# MCB-NINA-B1-v2_0_0.net
KiCad netlist of a schematic drawn in EAGLE
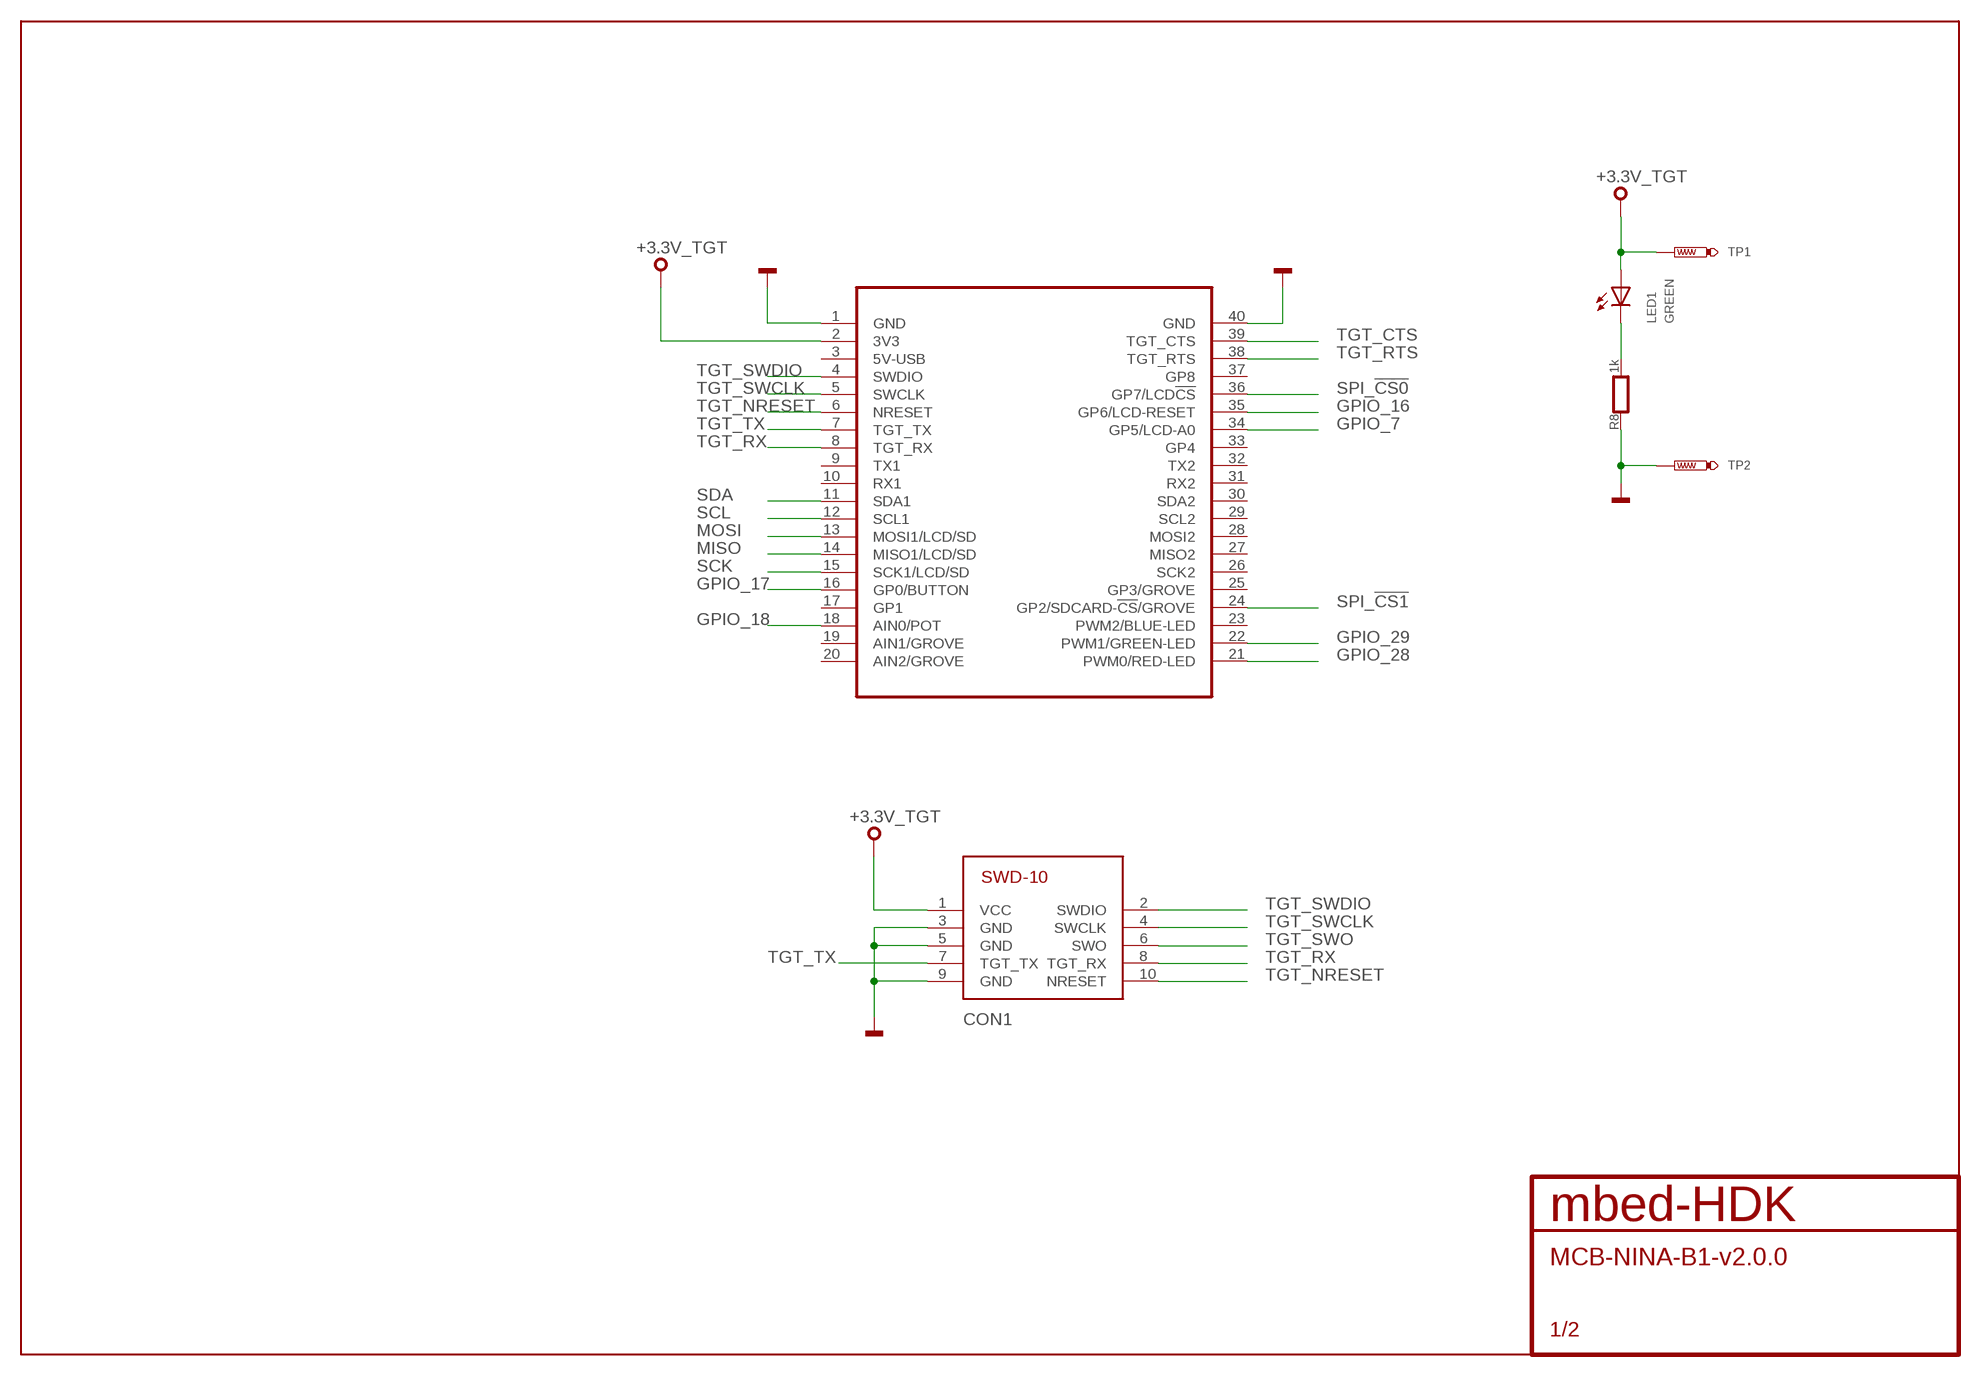
[diagram p0: schematic, sheet 1]
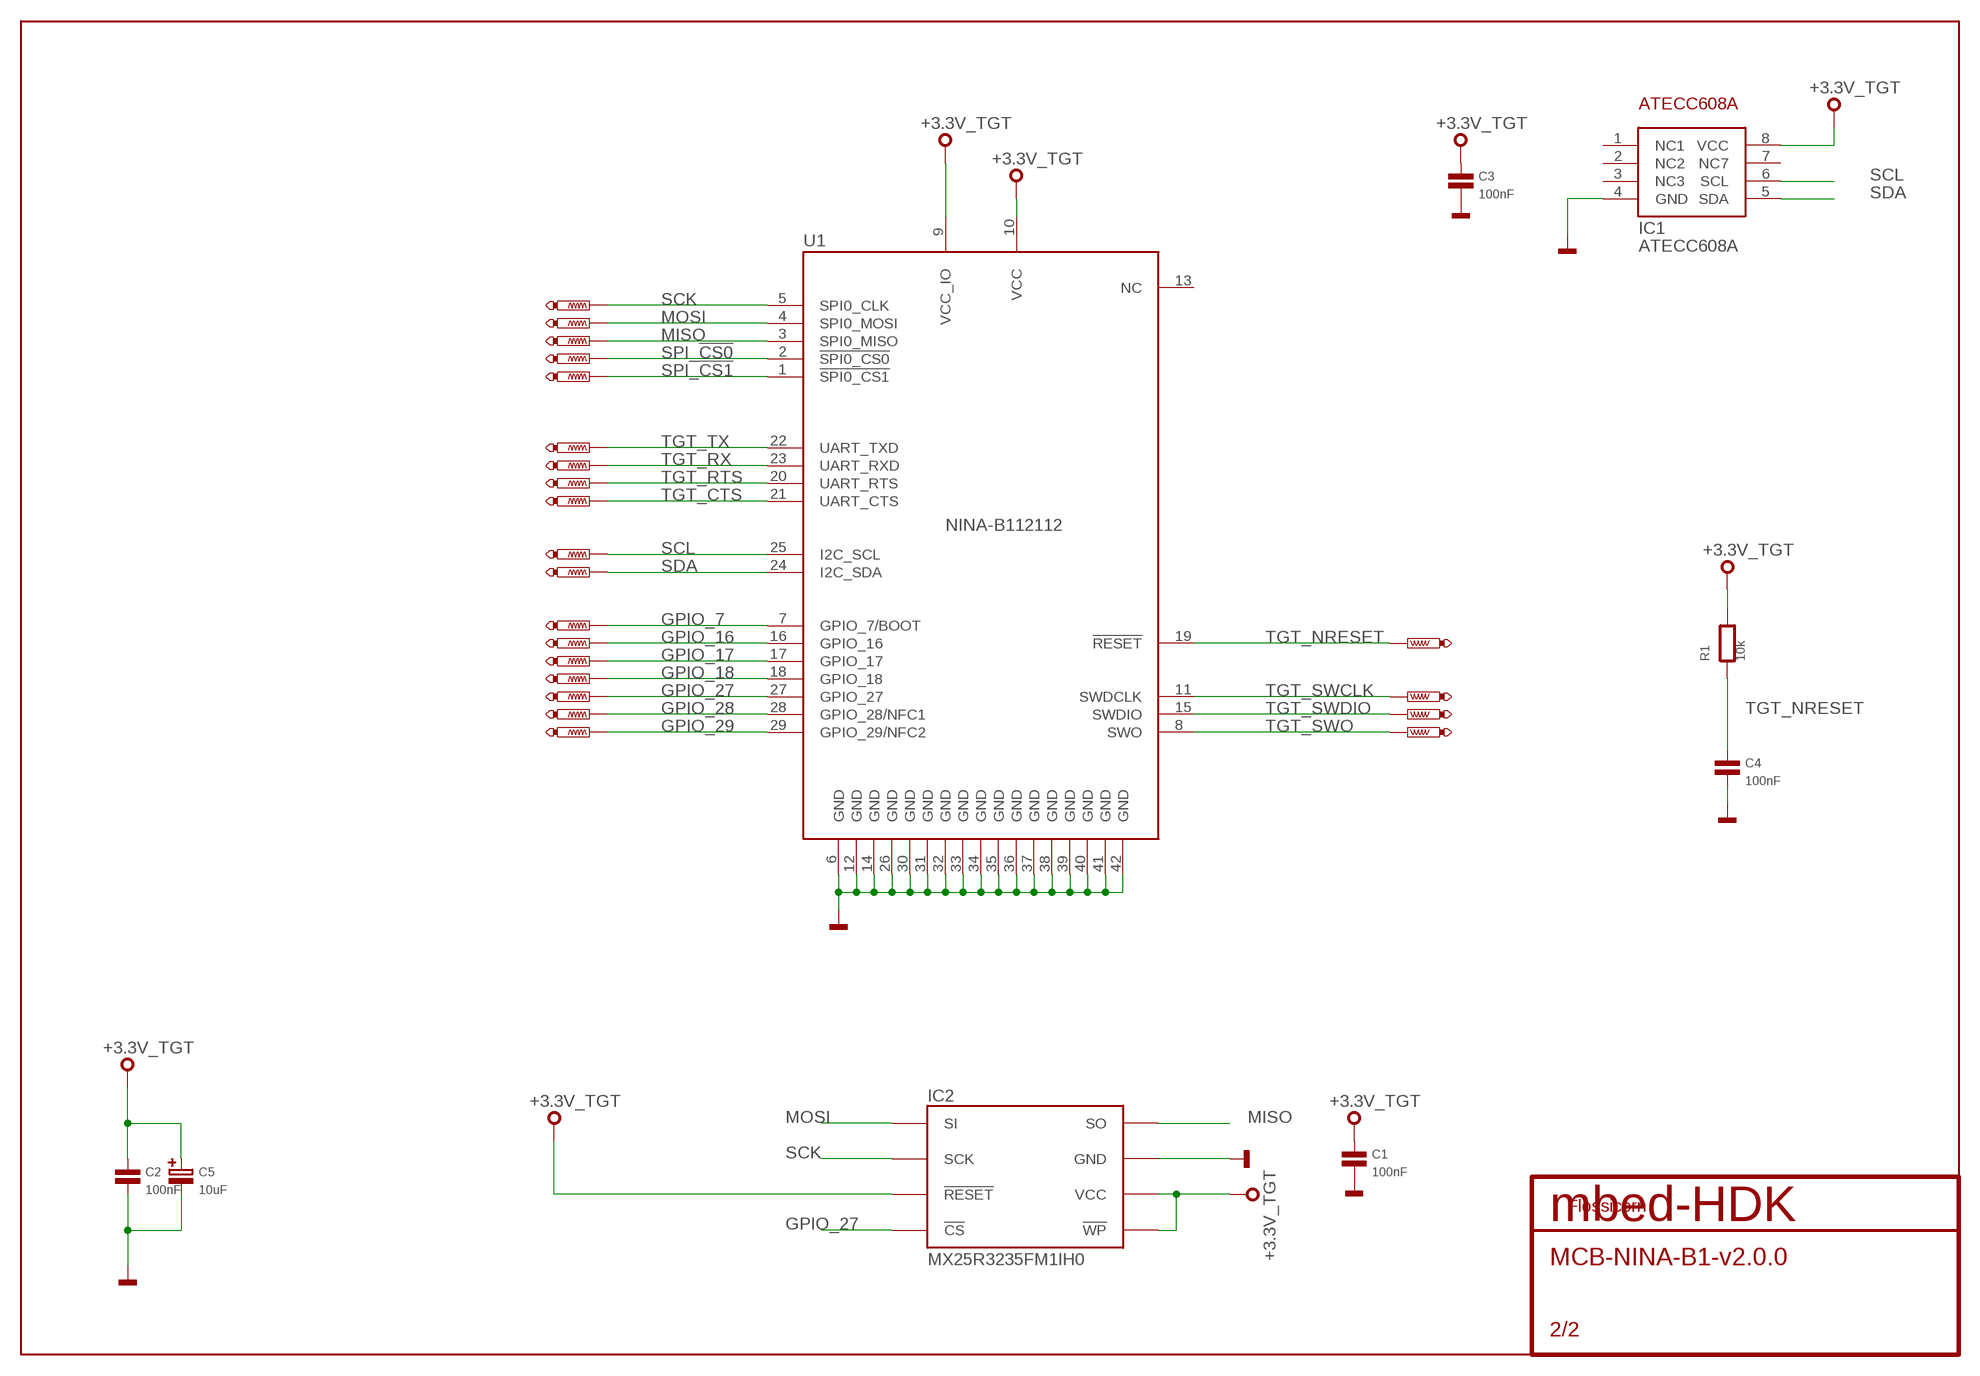
[diagram p1: schematic, sheet 2]

(export (version "E")
  (design (tool "Eeschema 10.0.6"))
  (components
    (comp (ref "C1")
      (value "100nF")
      (footprint "eagle-import:0603")
      (libsource (lib "eagle-import") (part "CAPACITOR0603"))
    )
    (comp (ref "C2")
      (value "100nF")
      (footprint "eagle-import:0603")
      (libsource (lib "eagle-import") (part "CAPACITOR0603"))
    )
    (comp (ref "C3")
      (value "100nF")
      (footprint "eagle-import:0603")
      (libsource (lib "eagle-import") (part "CAPACITOR0603"))
    )
    (comp (ref "C4")
      (value "100nF")
      (footprint "eagle-import:0603")
      (libsource (lib "eagle-import") (part "CAPACITOR0603"))
    )
    (comp (ref "C5")
      (value "10uF")
      (footprint "eagle-import:SMC_B")
      (fields (field (name "MF") "Kemet"))
      (libsource (lib "eagle-import") (part "CAPACITOR-POLARISEDB"))
    )
    (comp (ref "IC1")
      (value "ATECC608A")
      (footprint "eagle-import:SO8")
      (libsource (lib "eagle-import") (part "ATECC608A"))
    )
    (comp (ref "IC2")
      (value "MX25R3235FM1IH0")
      (footprint "eagle-import:SO8")
      (fields (field (name "MF") "Macronix"))
      (libsource (lib "eagle-import") (part "MX25R3235FM1IH0"))
    )
    (comp (ref "R1")
      (value "10k")
      (footprint "eagle-import:0603")
      (libsource (lib "eagle-import") (part "RESISTOR0603"))
    )
    (comp (ref "SS1")
      (value "FLOSSICORN0.5")
      (footprint "eagle-import:FLOSSICORN-0.5")
      (libsource (lib "eagle-import") (part "FLOSSICORN0.5"))
    )
    (comp (ref "TP3")
      (value "PTR1B1,27")
      (footprint "eagle-import:B1,27")
      (libsource (lib "eagle-import") (part "PTR1B1,27"))
    )
    (comp (ref "TP4")
      (value "PTR1B1,27")
      (footprint "eagle-import:B1,27")
      (libsource (lib "eagle-import") (part "PTR1B1,27"))
    )
    (comp (ref "TP5")
      (value "PTR1B1,27")
      (footprint "eagle-import:B1,27")
      (libsource (lib "eagle-import") (part "PTR1B1,27"))
    )
    (comp (ref "TP6")
      (value "PTR1B1,27")
      (footprint "eagle-import:B1,27")
      (libsource (lib "eagle-import") (part "PTR1B1,27"))
    )
    (comp (ref "TP7")
      (value "PTR1B1,27")
      (footprint "eagle-import:B1,27")
      (libsource (lib "eagle-import") (part "PTR1B1,27"))
    )
    (comp (ref "TP8")
      (value "PTR1B1,27")
      (footprint "eagle-import:B1,27")
      (libsource (lib "eagle-import") (part "PTR1B1,27"))
    )
    (comp (ref "TP9")
      (value "PTR1B1,27")
      (footprint "eagle-import:B1,27")
      (libsource (lib "eagle-import") (part "PTR1B1,27"))
    )
    (comp (ref "TP10")
      (value "PTR1B1,27")
      (footprint "eagle-import:B1,27")
      (libsource (lib "eagle-import") (part "PTR1B1,27"))
    )
    (comp (ref "TP11")
      (value "PTR1B1,27")
      (footprint "eagle-import:B1,27")
      (libsource (lib "eagle-import") (part "PTR1B1,27"))
    )
    (comp (ref "TP12")
      (value "PTR1B1,27")
      (footprint "eagle-import:B1,27")
      (libsource (lib "eagle-import") (part "PTR1B1,27"))
    )
    (comp (ref "TP13")
      (value "PTR1B1,27")
      (footprint "eagle-import:B1,27")
      (libsource (lib "eagle-import") (part "PTR1B1,27"))
    )
    (comp (ref "TP14")
      (value "PTR1B1,27")
      (footprint "eagle-import:B1,27")
      (libsource (lib "eagle-import") (part "PTR1B1,27"))
    )
    (comp (ref "TP15")
      (value "PTR1B1,27")
      (footprint "eagle-import:B1,27")
      (libsource (lib "eagle-import") (part "PTR1B1,27"))
    )
    (comp (ref "TP16")
      (value "PTR1B1,27")
      (footprint "eagle-import:B1,27")
      (libsource (lib "eagle-import") (part "PTR1B1,27"))
    )
    (comp (ref "TP17")
      (value "PTR1B1,27")
      (footprint "eagle-import:B1,27")
      (libsource (lib "eagle-import") (part "PTR1B1,27"))
    )
    (comp (ref "TP18")
      (value "PTR1B1,27")
      (footprint "eagle-import:B1,27")
      (libsource (lib "eagle-import") (part "PTR1B1,27"))
    )
    (comp (ref "TP19")
      (value "PTR1B1,27")
      (footprint "eagle-import:B1,27")
      (libsource (lib "eagle-import") (part "PTR1B1,27"))
    )
    (comp (ref "TP20")
      (value "PTR1B1,27")
      (footprint "eagle-import:B1,27")
      (libsource (lib "eagle-import") (part "PTR1B1,27"))
    )
    (comp (ref "TP21")
      (value "PTR1B1,27")
      (footprint "eagle-import:B1,27")
      (libsource (lib "eagle-import") (part "PTR1B1,27"))
    )
    (comp (ref "TP22")
      (value "PTR1B1,27")
      (footprint "eagle-import:B1,27")
      (libsource (lib "eagle-import") (part "PTR1B1,27"))
    )
    (comp (ref "TP23")
      (value "PTR1B1,27")
      (footprint "eagle-import:B1,27")
      (libsource (lib "eagle-import") (part "PTR1B1,27"))
    )
    (comp (ref "TP24")
      (value "PTR1B1,27")
      (footprint "eagle-import:B1,27")
      (libsource (lib "eagle-import") (part "PTR1B1,27"))
    )
    (comp (ref "U1")
      (value "NINA-B112112")
      (footprint "eagle-import:NINA112-42")
      (libsource (lib "eagle-import") (part "NINA-B112112"))
    )
    (comp (ref "CON1")
      (value "SWD-10/TC2050_SMD")
      (footprint "eagle-import:FTSH-105-02")
      (libsource (lib "eagle-import") (part "SWD-10/TC2050_SMD"))
    )
    (comp (ref "LED1")
      (value "GREEN")
      (footprint "eagle-import:CHIPLED_0603")
      (fields (field (name "MF") "Wurth Electronics Inc"))
      (libsource (lib "eagle-import") (part "SMD_LED0603"))
    )
    (comp (ref "MOD1")
      (value "MODULE_DAUGHTER")
      (footprint "eagle-import:MODULE_DAUGHTER")
      (libsource (lib "eagle-import") (part "MODULE_DAUGHTER"))
    )
    (comp (ref "R8")
      (value "1k")
      (footprint "eagle-import:0603")
      (libsource (lib "eagle-import") (part "RESISTOR0603"))
    )
    (comp (ref "TP1")
      (value "TEST-POINT-50R-PTH")
      (footprint "eagle-import:TP50-PTH")
      (libsource (lib "eagle-import") (part "TEST-POINT-50R-PTH"))
    )
    (comp (ref "TP2")
      (value "TEST-POINT-50R-PTH")
      (footprint "eagle-import:TP50-PTH")
      (libsource (lib "eagle-import") (part "TEST-POINT-50R-PTH"))
    )
  )
  (nets
    (net (code "1") (name "+3.3V_TGT") (class "Default")
      (node (ref "C1") (pin "1") (pinfunction "P$1_1") (pintype "passive"))
      (node (ref "C2") (pin "1") (pinfunction "P$1_1") (pintype "passive"))
      (node (ref "C3") (pin "1") (pinfunction "P$1_1") (pintype "passive"))
      (node (ref "C5") (pin "+") (pinfunction "+_+") (pintype "passive"))
      (node (ref "CON1") (pin "1") (pinfunction "VCC_1") (pintype "bidirectional"))
      (node (ref "IC1") (pin "8") (pinfunction "VCC_8") (pintype "bidirectional"))
      (node (ref "IC2") (pin "3") (pinfunction "~{WP}_3") (pintype "bidirectional"))
      (node (ref "IC2") (pin "7") (pinfunction "~{RESET}_7") (pintype "bidirectional"))
      (node (ref "IC2") (pin "8") (pinfunction "VCC_8") (pintype "bidirectional"))
      (node (ref "LED1") (pin "A") (pinfunction "A_A") (pintype "passive"))
      (node (ref "MOD1") (pin "2") (pinfunction "3V3_2") (pintype "bidirectional"))
      (node (ref "R1") (pin "2") (pinfunction "P$2_2") (pintype "passive"))
      (node (ref "TP1") (pin "TP") (pinfunction "TP_TP") (pintype "input"))
      (node (ref "U1") (pin "10") (pinfunction "VCC_10") (pintype "power_in"))
      (node (ref "U1") (pin "9") (pinfunction "VCC_IO_9") (pintype "power_in"))
    )
    (net (code "2") (name "GND") (class "Default")
      (node (ref "C1") (pin "2") (pinfunction "P$2_2") (pintype "passive"))
      (node (ref "C2") (pin "2") (pinfunction "P$2_2") (pintype "passive"))
      (node (ref "C3") (pin "2") (pinfunction "P$2_2") (pintype "passive"))
      (node (ref "C4") (pin "2") (pinfunction "P$2_2") (pintype "passive"))
      (node (ref "C5") (pin "-") (pinfunction "-_-") (pintype "passive"))
      (node (ref "CON1") (pin "3") (pinfunction "GND_3") (pintype "bidirectional"))
      (node (ref "CON1") (pin "5") (pinfunction "GND_5") (pintype "bidirectional"))
      (node (ref "CON1") (pin "9") (pinfunction "GND_9") (pintype "bidirectional"))
      (node (ref "IC1") (pin "4") (pinfunction "GND_4") (pintype "bidirectional"))
      (node (ref "IC2") (pin "4") (pinfunction "GND_4") (pintype "bidirectional"))
      (node (ref "MOD1") (pin "1") (pinfunction "GND_1") (pintype "bidirectional"))
      (node (ref "MOD1") (pin "40") (pinfunction "GND_40") (pintype "bidirectional"))
      (node (ref "R8") (pin "1") (pinfunction "P$1_1") (pintype "passive"))
      (node (ref "TP2") (pin "TP") (pinfunction "TP_TP") (pintype "input"))
      (node (ref "U1") (pin "12") (pinfunction "GND_12") (pintype "power_in"))
      (node (ref "U1") (pin "14") (pinfunction "GND_14") (pintype "power_in"))
      (node (ref "U1") (pin "26") (pinfunction "GND_26") (pintype "power_in"))
      (node (ref "U1") (pin "30") (pinfunction "GND_30") (pintype "power_in"))
      (node (ref "U1") (pin "31") (pinfunction "GND_31") (pintype "power_in"))
      (node (ref "U1") (pin "32") (pinfunction "GND_32") (pintype "power_in"))
      (node (ref "U1") (pin "33") (pinfunction "GND_33") (pintype "power_in"))
      (node (ref "U1") (pin "34") (pinfunction "GND_34") (pintype "power_in"))
      (node (ref "U1") (pin "35") (pinfunction "GND_35") (pintype "power_in"))
      (node (ref "U1") (pin "36") (pinfunction "GND_36") (pintype "power_in"))
      (node (ref "U1") (pin "37") (pinfunction "GND_37") (pintype "power_in"))
      (node (ref "U1") (pin "38") (pinfunction "GND_38") (pintype "power_in"))
      (node (ref "U1") (pin "39") (pinfunction "GND_39") (pintype "power_in"))
      (node (ref "U1") (pin "40") (pinfunction "GND_40") (pintype "power_in"))
      (node (ref "U1") (pin "41") (pinfunction "GND_41") (pintype "power_in"))
      (node (ref "U1") (pin "42") (pinfunction "GND_42") (pintype "power_in"))
      (node (ref "U1") (pin "6") (pinfunction "GND_6") (pintype "power_in"))
    )
    (net (code "3") (name "GPIO_7") (class "Default")
      (node (ref "MOD1") (pin "34") (pinfunction "GP5/LCD-A0_34") (pintype "bidirectional"))
      (node (ref "TP14") (pin "TP") (pinfunction "TP_TP") (pintype "input"))
      (node (ref "U1") (pin "7") (pinfunction "GPIO_7/BOOT_7") (pintype "bidirectional"))
    )
    (net (code "4") (name "GPIO_16") (class "Default")
      (node (ref "MOD1") (pin "35") (pinfunction "GP6/LCD-RESET_35") (pintype "bidirectional"))
      (node (ref "TP15") (pin "TP") (pinfunction "TP_TP") (pintype "input"))
      (node (ref "U1") (pin "16") (pinfunction "GPIO_16_16") (pintype "bidirectional"))
    )
    (net (code "5") (name "GPIO_17") (class "Default")
      (node (ref "MOD1") (pin "16") (pinfunction "GP0/BUTTON_16") (pintype "bidirectional"))
      (node (ref "TP16") (pin "TP") (pinfunction "TP_TP") (pintype "input"))
      (node (ref "U1") (pin "17") (pinfunction "GPIO_17_17") (pintype "bidirectional"))
    )
    (net (code "6") (name "GPIO_18") (class "Default")
      (node (ref "MOD1") (pin "18") (pinfunction "AIN0/POT_18") (pintype "bidirectional"))
      (node (ref "TP17") (pin "TP") (pinfunction "TP_TP") (pintype "input"))
      (node (ref "U1") (pin "18") (pinfunction "GPIO_18_18") (pintype "bidirectional"))
    )
    (net (code "7") (name "GPIO_27") (class "Default")
      (node (ref "IC2") (pin "1") (pinfunction "~{CS}_1") (pintype "bidirectional"))
      (node (ref "TP18") (pin "TP") (pinfunction "TP_TP") (pintype "input"))
      (node (ref "U1") (pin "27") (pinfunction "GPIO_27_27") (pintype "bidirectional"))
    )
    (net (code "8") (name "GPIO_28") (class "Default")
      (node (ref "MOD1") (pin "21") (pinfunction "PWM0/RED-LED_21") (pintype "bidirectional"))
      (node (ref "TP19") (pin "TP") (pinfunction "TP_TP") (pintype "input"))
      (node (ref "U1") (pin "28") (pinfunction "GPIO_28/NFC1_28") (pintype "bidirectional"))
    )
    (net (code "9") (name "GPIO_29") (class "Default")
      (node (ref "MOD1") (pin "22") (pinfunction "PWM1/GREEN-LED_22") (pintype "bidirectional"))
      (node (ref "TP20") (pin "TP") (pinfunction "TP_TP") (pintype "input"))
      (node (ref "U1") (pin "29") (pinfunction "GPIO_29/NFC2_29") (pintype "bidirectional"))
    )
    (net (code "10") (name "MISO") (class "Default")
      (node (ref "IC2") (pin "2") (pinfunction "SO_2") (pintype "bidirectional"))
      (node (ref "MOD1") (pin "14") (pinfunction "MISO1/LCD/SD_14") (pintype "bidirectional"))
      (node (ref "TP5") (pin "TP") (pinfunction "TP_TP") (pintype "input"))
      (node (ref "U1") (pin "3") (pinfunction "SPI0_MISO_3") (pintype "bidirectional"))
    )
    (net (code "11") (name "MOSI") (class "Default")
      (node (ref "IC2") (pin "5") (pinfunction "SI_5") (pintype "bidirectional"))
      (node (ref "MOD1") (pin "13") (pinfunction "MOSI1/LCD/SD_13") (pintype "bidirectional"))
      (node (ref "TP4") (pin "TP") (pinfunction "TP_TP") (pintype "input"))
      (node (ref "U1") (pin "4") (pinfunction "SPI0_MOSI_4") (pintype "bidirectional"))
    )
    (net (code "12") (name "Net-(R8-P$2)") (class "Default")
      (node (ref "LED1") (pin "C") (pinfunction "C_C") (pintype "passive"))
      (node (ref "R8") (pin "2") (pinfunction "P$2_2") (pintype "passive"))
    )
    (net (code "13") (name "SCK") (class "Default")
      (node (ref "IC2") (pin "6") (pinfunction "SCK_6") (pintype "bidirectional"))
      (node (ref "MOD1") (pin "15") (pinfunction "SCK1/LCD/SD_15") (pintype "bidirectional"))
      (node (ref "TP3") (pin "TP") (pinfunction "TP_TP") (pintype "input"))
      (node (ref "U1") (pin "5") (pinfunction "SPI0_CLK_5") (pintype "bidirectional"))
    )
    (net (code "14") (name "SCL") (class "Default")
      (node (ref "IC1") (pin "6") (pinfunction "SCL_6") (pintype "bidirectional"))
      (node (ref "MOD1") (pin "12") (pinfunction "SCL1_12") (pintype "bidirectional"))
      (node (ref "TP12") (pin "TP") (pinfunction "TP_TP") (pintype "input"))
      (node (ref "U1") (pin "25") (pinfunction "I2C_SCL_25") (pintype "bidirectional"))
    )
    (net (code "15") (name "SDA") (class "Default")
      (node (ref "IC1") (pin "5") (pinfunction "SDA_5") (pintype "bidirectional"))
      (node (ref "MOD1") (pin "11") (pinfunction "SDA1_11") (pintype "bidirectional"))
      (node (ref "TP13") (pin "TP") (pinfunction "TP_TP") (pintype "input"))
      (node (ref "U1") (pin "24") (pinfunction "I2C_SDA_24") (pintype "bidirectional"))
    )
    (net (code "16") (name "SPI_~{CS0}") (class "Default")
      (node (ref "MOD1") (pin "36") (pinfunction "GP7/LCD~{CS}_36") (pintype "bidirectional"))
      (node (ref "TP6") (pin "TP") (pinfunction "TP_TP") (pintype "input"))
      (node (ref "U1") (pin "2") (pinfunction "~{SPI0_CS0}_2") (pintype "bidirectional"))
    )
    (net (code "17") (name "SPI_~{CS1}") (class "Default")
      (node (ref "MOD1") (pin "24") (pinfunction "GP2/SDCARD-~{CS}/GROVE_24") (pintype "bidirectional"))
      (node (ref "TP7") (pin "TP") (pinfunction "TP_TP") (pintype "input"))
      (node (ref "U1") (pin "1") (pinfunction "~{SPI0_CS1}_1") (pintype "output"))
    )
    (net (code "18") (name "TGT_CTS") (class "Default")
      (node (ref "MOD1") (pin "39") (pinfunction "TGT_CTS_39") (pintype "bidirectional"))
      (node (ref "TP11") (pin "TP") (pinfunction "TP_TP") (pintype "input"))
      (node (ref "U1") (pin "21") (pinfunction "UART_CTS_21") (pintype "bidirectional"))
    )
    (net (code "19") (name "TGT_NRESET") (class "Default")
      (node (ref "C4") (pin "1") (pinfunction "P$1_1") (pintype "passive"))
      (node (ref "CON1") (pin "10") (pinfunction "NRESET_10") (pintype "bidirectional"))
      (node (ref "MOD1") (pin "6") (pinfunction "NRESET_6") (pintype "bidirectional"))
      (node (ref "R1") (pin "1") (pinfunction "P$1_1") (pintype "passive"))
      (node (ref "TP21") (pin "TP") (pinfunction "TP_TP") (pintype "input"))
      (node (ref "U1") (pin "19") (pinfunction "~{RESET}_19") (pintype "input"))
    )
    (net (code "20") (name "TGT_RTS") (class "Default")
      (node (ref "MOD1") (pin "38") (pinfunction "TGT_RTS_38") (pintype "bidirectional"))
      (node (ref "TP10") (pin "TP") (pinfunction "TP_TP") (pintype "input"))
      (node (ref "U1") (pin "20") (pinfunction "UART_RTS_20") (pintype "bidirectional"))
    )
    (net (code "21") (name "TGT_RX") (class "Default")
      (node (ref "CON1") (pin "8") (pinfunction "TGT_RX_8") (pintype "bidirectional"))
      (node (ref "MOD1") (pin "8") (pinfunction "TGT_RX_8") (pintype "bidirectional"))
      (node (ref "TP9") (pin "TP") (pinfunction "TP_TP") (pintype "input"))
      (node (ref "U1") (pin "23") (pinfunction "UART_RXD_23") (pintype "bidirectional"))
    )
    (net (code "22") (name "TGT_SWCLK") (class "Default")
      (node (ref "CON1") (pin "4") (pinfunction "SWCLK_4") (pintype "bidirectional"))
      (node (ref "MOD1") (pin "5") (pinfunction "SWCLK_5") (pintype "bidirectional"))
      (node (ref "TP22") (pin "TP") (pinfunction "TP_TP") (pintype "input"))
      (node (ref "U1") (pin "11") (pinfunction "SWDCLK_11") (pintype "input"))
    )
    (net (code "23") (name "TGT_SWDIO") (class "Default")
      (node (ref "CON1") (pin "2") (pinfunction "SWDIO_2") (pintype "bidirectional"))
      (node (ref "MOD1") (pin "4") (pinfunction "SWDIO_4") (pintype "bidirectional"))
      (node (ref "TP23") (pin "TP") (pinfunction "TP_TP") (pintype "input"))
      (node (ref "U1") (pin "15") (pinfunction "SWDIO_15") (pintype "bidirectional"))
    )
    (net (code "24") (name "TGT_SWO") (class "Default")
      (node (ref "CON1") (pin "6") (pinfunction "SWO_6") (pintype "bidirectional"))
      (node (ref "TP24") (pin "TP") (pinfunction "TP_TP") (pintype "input"))
      (node (ref "U1") (pin "8") (pinfunction "SWO_8") (pintype "output"))
    )
    (net (code "25") (name "TGT_TX") (class "Default")
      (node (ref "CON1") (pin "7") (pinfunction "TGT_TX_7") (pintype "bidirectional"))
      (node (ref "MOD1") (pin "7") (pinfunction "TGT_TX_7") (pintype "bidirectional"))
      (node (ref "TP8") (pin "TP") (pinfunction "TP_TP") (pintype "input"))
      (node (ref "U1") (pin "22") (pinfunction "UART_TXD_22") (pintype "bidirectional"))
    )
    (net (code "26") (name "unconnected-(IC1-NC1-Pad1)") (class "Default")
      (node (ref "IC1") (pin "1") (pinfunction "NC1_1") (pintype "bidirectional"))
    )
    (net (code "27") (name "unconnected-(IC1-NC2-Pad2)") (class "Default")
      (node (ref "IC1") (pin "2") (pinfunction "NC2_2") (pintype "bidirectional"))
    )
    (net (code "28") (name "unconnected-(IC1-NC3-Pad3)") (class "Default")
      (node (ref "IC1") (pin "3") (pinfunction "NC3_3") (pintype "bidirectional"))
    )
    (net (code "29") (name "unconnected-(IC1-NC7-Pad7)") (class "Default")
      (node (ref "IC1") (pin "7") (pinfunction "NC7_7") (pintype "bidirectional"))
    )
    (net (code "30") (name "unconnected-(MOD1-5V-USB-Pad3)") (class "Default")
      (node (ref "MOD1") (pin "3") (pinfunction "5V-USB_3") (pintype "bidirectional"))
    )
    (net (code "31") (name "unconnected-(MOD1-AIN1{slash}GROVE-Pad19)") (class "Default")
      (node (ref "MOD1") (pin "19") (pinfunction "AIN1/GROVE_19") (pintype "bidirectional"))
    )
    (net (code "32") (name "unconnected-(MOD1-AIN2{slash}GROVE-Pad20)") (class "Default")
      (node (ref "MOD1") (pin "20") (pinfunction "AIN2/GROVE_20") (pintype "bidirectional"))
    )
    (net (code "33") (name "unconnected-(MOD1-GP1-Pad17)") (class "Default")
      (node (ref "MOD1") (pin "17") (pinfunction "GP1_17") (pintype "bidirectional"))
    )
    (net (code "34") (name "unconnected-(MOD1-GP3{slash}GROVE-Pad25)") (class "Default")
      (node (ref "MOD1") (pin "25") (pinfunction "GP3/GROVE_25") (pintype "bidirectional"))
    )
    (net (code "35") (name "unconnected-(MOD1-GP4-Pad33)") (class "Default")
      (node (ref "MOD1") (pin "33") (pinfunction "GP4_33") (pintype "bidirectional"))
    )
    (net (code "36") (name "unconnected-(MOD1-GP8-Pad37)") (class "Default")
      (node (ref "MOD1") (pin "37") (pinfunction "GP8_37") (pintype "bidirectional"))
    )
    (net (code "37") (name "unconnected-(MOD1-MISO2-Pad27)") (class "Default")
      (node (ref "MOD1") (pin "27") (pinfunction "MISO2_27") (pintype "bidirectional"))
    )
    (net (code "38") (name "unconnected-(MOD1-MOSI2-Pad28)") (class "Default")
      (node (ref "MOD1") (pin "28") (pinfunction "MOSI2_28") (pintype "bidirectional"))
    )
    (net (code "39") (name "unconnected-(MOD1-PWM2{slash}BLUE-LED-Pad23)") (class "Default")
      (node (ref "MOD1") (pin "23") (pinfunction "PWM2/BLUE-LED_23") (pintype "bidirectional"))
    )
    (net (code "40") (name "unconnected-(MOD1-RX1-Pad10)") (class "Default")
      (node (ref "MOD1") (pin "10") (pinfunction "RX1_10") (pintype "bidirectional"))
    )
    (net (code "41") (name "unconnected-(MOD1-RX2-Pad31)") (class "Default")
      (node (ref "MOD1") (pin "31") (pinfunction "RX2_31") (pintype "bidirectional"))
    )
    (net (code "42") (name "unconnected-(MOD1-SCK2-Pad26)") (class "Default")
      (node (ref "MOD1") (pin "26") (pinfunction "SCK2_26") (pintype "bidirectional"))
    )
    (net (code "43") (name "unconnected-(MOD1-SCL2-Pad29)") (class "Default")
      (node (ref "MOD1") (pin "29") (pinfunction "SCL2_29") (pintype "bidirectional"))
    )
    (net (code "44") (name "unconnected-(MOD1-SDA2-Pad30)") (class "Default")
      (node (ref "MOD1") (pin "30") (pinfunction "SDA2_30") (pintype "bidirectional"))
    )
    (net (code "45") (name "unconnected-(MOD1-TX1-Pad9)") (class "Default")
      (node (ref "MOD1") (pin "9") (pinfunction "TX1_9") (pintype "bidirectional"))
    )
    (net (code "46") (name "unconnected-(MOD1-TX2-Pad32)") (class "Default")
      (node (ref "MOD1") (pin "32") (pinfunction "TX2_32") (pintype "bidirectional"))
    )
    (net (code "47") (name "unconnected-(U1-NC-Pad13)") (class "Default")
      (node (ref "U1") (pin "13") (pinfunction "NC_13") (pintype "no_connect"))
    )
  )
)
